# ADNS-9800.net
KiCad netlist of a schematic drawn in EAGLE
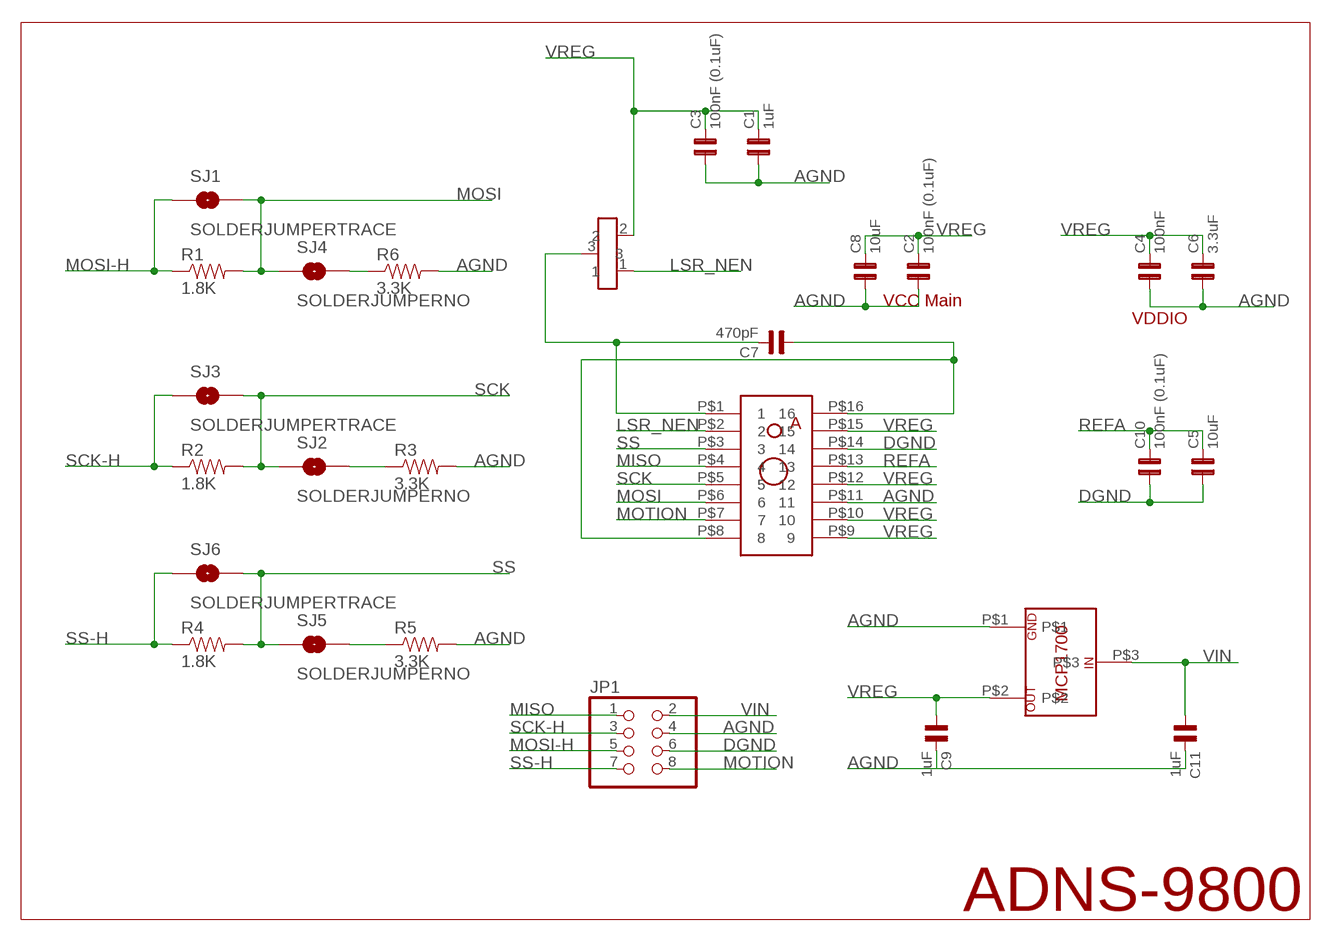
[diagram p0: schematic, sheet 1]

(export (version "E")
  (design (tool "Eeschema 10.0.6"))
  (components
    (comp (ref "C1")
      (value "1uF")
      (footprint "eagle-import:0603")
      (libsource (lib "eagle-import") (part "C0603"))
    )
    (comp (ref "C2")
      (value "100nF (0.1uF)")
      (footprint "eagle-import:0603")
      (libsource (lib "eagle-import") (part "C0603"))
    )
    (comp (ref "C3")
      (value "100nF (0.1uF)")
      (footprint "eagle-import:0603")
      (libsource (lib "eagle-import") (part "C0603"))
    )
    (comp (ref "C4")
      (value "100nF")
      (footprint "eagle-import:0603")
      (libsource (lib "eagle-import") (part "C0603"))
    )
    (comp (ref "C5")
      (value "10uF")
      (footprint "eagle-import:0603")
      (libsource (lib "eagle-import") (part "C0603"))
    )
    (comp (ref "C6")
      (value "3.3uF")
      (footprint "eagle-import:0603")
      (libsource (lib "eagle-import") (part "C0603"))
    )
    (comp (ref "C7")
      (value "470pF")
      (footprint "eagle-import:0603")
      (libsource (lib "eagle-import") (part "C0603"))
    )
    (comp (ref "C8")
      (value "10uF")
      (footprint "eagle-import:0603")
      (libsource (lib "eagle-import") (part "C0603"))
    )
    (comp (ref "C9")
      (value "1uF")
      (footprint "eagle-import:0603")
      (libsource (lib "eagle-import") (part "C0603"))
    )
    (comp (ref "C10")
      (value "100nF (0.1uF)")
      (footprint "eagle-import:0603")
      (libsource (lib "eagle-import") (part "C0603"))
    )
    (comp (ref "C11")
      (value "1uF")
      (footprint "eagle-import:0603")
      (libsource (lib "eagle-import") (part "C0603"))
    )
    (comp (ref "JP1")
      (value "PINHD-2X4")
      (footprint "eagle-import:2X04")
      (libsource (lib "eagle-import") (part "PINHD-2X4"))
    )
    (comp (ref "Q1")
      (value "TRANSISTOR_SC-75")
      (footprint "eagle-import:SC-75_TRANSISTOR")
      (libsource (lib "eagle-import") (part "TRANSISTOR_SC-75"))
    )
    (comp (ref "R1")
      (value "1.8K")
      (footprint "eagle-import:0603-RES")
      (libsource (lib "eagle-import") (part "RESISTOR0603-RES"))
    )
    (comp (ref "R2")
      (value "1.8K")
      (footprint "eagle-import:0603-RES")
      (libsource (lib "eagle-import") (part "RESISTOR0603-RES"))
    )
    (comp (ref "R3")
      (value "3.3K")
      (footprint "eagle-import:0603-RES")
      (libsource (lib "eagle-import") (part "RESISTOR0603-RES"))
    )
    (comp (ref "R4")
      (value "1.8K")
      (footprint "eagle-import:0603-RES")
      (libsource (lib "eagle-import") (part "RESISTOR0603-RES"))
    )
    (comp (ref "R5")
      (value "3.3K")
      (footprint "eagle-import:0603-RES")
      (libsource (lib "eagle-import") (part "RESISTOR0603-RES"))
    )
    (comp (ref "R6")
      (value "3.3K")
      (footprint "eagle-import:0603-RES")
      (libsource (lib "eagle-import") (part "RESISTOR0603-RES"))
    )
    (comp (ref "SJ1")
      (value "SOLDERJUMPERTRACE")
      (footprint "eagle-import:SJ_2S-TRACE")
      (libsource (lib "eagle-import") (part "SOLDERJUMPERTRACE"))
    )
    (comp (ref "SJ2")
      (value "SOLDERJUMPERNO")
      (footprint "eagle-import:SJ_2S-NO")
      (libsource (lib "eagle-import") (part "SOLDERJUMPERNO"))
    )
    (comp (ref "SJ3")
      (value "SOLDERJUMPERTRACE")
      (footprint "eagle-import:SJ_2S-TRACE")
      (libsource (lib "eagle-import") (part "SOLDERJUMPERTRACE"))
    )
    (comp (ref "SJ4")
      (value "SOLDERJUMPERNO")
      (footprint "eagle-import:SJ_2S-NO")
      (libsource (lib "eagle-import") (part "SOLDERJUMPERNO"))
    )
    (comp (ref "SJ5")
      (value "SOLDERJUMPERNO")
      (footprint "eagle-import:SJ_2S-NO")
      (libsource (lib "eagle-import") (part "SOLDERJUMPERNO"))
    )
    (comp (ref "SJ6")
      (value "SOLDERJUMPERTRACE")
      (footprint "eagle-import:SJ_2S-TRACE")
      (libsource (lib "eagle-import") (part "SOLDERJUMPERTRACE"))
    )
    (comp (ref "U$1")
      (value "AVAGO_ADNS-9500")
      (footprint "eagle-import:AVAGO_ADNS-9500")
      (libsource (lib "eagle-import") (part "AVAGO_ADNS-9500"))
    )
    (comp (ref "U$2")
      (value "MCP1700__LDO")
      (footprint "eagle-import:MCP1700__LDO")
      (libsource (lib "eagle-import") (part "MCP1700__LDO"))
    )
  )
  (nets
    (net (code "1") (name "/AGND") (class "Default")
      (node (ref "C1") (pin "1") (pinfunction "1_1") (pintype "passive"))
      (node (ref "C11") (pin "2") (pinfunction "2_2") (pintype "passive"))
      (node (ref "C2") (pin "1") (pinfunction "1_1") (pintype "passive"))
      (node (ref "C3") (pin "1") (pinfunction "1_1") (pintype "passive"))
      (node (ref "C4") (pin "1") (pinfunction "1_1") (pintype "passive"))
      (node (ref "C6") (pin "1") (pinfunction "1_1") (pintype "passive"))
      (node (ref "C8") (pin "1") (pinfunction "1_1") (pintype "passive"))
      (node (ref "C9") (pin "2") (pinfunction "2_2") (pintype "passive"))
      (node (ref "JP1") (pin "4") (pinfunction "4_4") (pintype "passive"))
      (node (ref "R3") (pin "2") (pinfunction "2_2") (pintype "passive"))
      (node (ref "R5") (pin "2") (pinfunction "2_2") (pintype "passive"))
      (node (ref "R6") (pin "2") (pinfunction "2_2") (pintype "passive"))
      (node (ref "U$1") (pin "P$11") (pinfunction "11_P$11") (pintype "bidirectional"))
      (node (ref "U$2") (pin "P$1") (pinfunction "P$1_P$1") (pintype "bidirectional"))
    )
    (net (code "2") (name "/DGND") (class "Default")
      (node (ref "C10") (pin "1") (pinfunction "1_1") (pintype "passive"))
      (node (ref "C5") (pin "1") (pinfunction "1_1") (pintype "passive"))
      (node (ref "JP1") (pin "6") (pinfunction "6_6") (pintype "passive"))
      (node (ref "U$1") (pin "P$14") (pinfunction "14_P$14") (pintype "bidirectional"))
    )
    (net (code "3") (name "/LSR_NEN") (class "Default")
      (node (ref "Q1") (pin "1") (pinfunction "1_1") (pintype "bidirectional"))
      (node (ref "U$1") (pin "P$2") (pinfunction "2_P$2") (pintype "bidirectional"))
    )
    (net (code "4") (name "/MISO") (class "Default")
      (node (ref "JP1") (pin "1") (pinfunction "1_1") (pintype "passive"))
      (node (ref "U$1") (pin "P$4") (pinfunction "4_P$4") (pintype "bidirectional"))
    )
    (net (code "5") (name "/MOSI") (class "Default")
      (node (ref "R1") (pin "2") (pinfunction "2_2") (pintype "passive"))
      (node (ref "SJ1") (pin "2") (pinfunction "2_2") (pintype "passive"))
      (node (ref "SJ4") (pin "1") (pinfunction "1_1") (pintype "passive"))
      (node (ref "U$1") (pin "P$6") (pinfunction "6_P$6") (pintype "bidirectional"))
    )
    (net (code "6") (name "/MOSI-H") (class "Default")
      (node (ref "JP1") (pin "5") (pinfunction "5_5") (pintype "passive"))
      (node (ref "R1") (pin "1") (pinfunction "1_1") (pintype "passive"))
      (node (ref "SJ1") (pin "1") (pinfunction "1_1") (pintype "passive"))
    )
    (net (code "7") (name "/MOTION") (class "Default")
      (node (ref "JP1") (pin "8") (pinfunction "8_8") (pintype "passive"))
      (node (ref "U$1") (pin "P$7") (pinfunction "7_P$7") (pintype "bidirectional"))
    )
    (net (code "8") (name "/REFA") (class "Default")
      (node (ref "C10") (pin "2") (pinfunction "2_2") (pintype "passive"))
      (node (ref "C5") (pin "2") (pinfunction "2_2") (pintype "passive"))
      (node (ref "U$1") (pin "P$13") (pinfunction "13_P$13") (pintype "bidirectional"))
    )
    (net (code "9") (name "/SCK") (class "Default")
      (node (ref "R2") (pin "2") (pinfunction "2_2") (pintype "passive"))
      (node (ref "SJ2") (pin "1") (pinfunction "1_1") (pintype "passive"))
      (node (ref "SJ3") (pin "2") (pinfunction "2_2") (pintype "passive"))
      (node (ref "U$1") (pin "P$5") (pinfunction "5_P$5") (pintype "bidirectional"))
    )
    (net (code "10") (name "/SCK-H") (class "Default")
      (node (ref "JP1") (pin "3") (pinfunction "3_3") (pintype "passive"))
      (node (ref "R2") (pin "1") (pinfunction "1_1") (pintype "passive"))
      (node (ref "SJ3") (pin "1") (pinfunction "1_1") (pintype "passive"))
    )
    (net (code "11") (name "/SS") (class "Default")
      (node (ref "R4") (pin "2") (pinfunction "2_2") (pintype "passive"))
      (node (ref "SJ5") (pin "1") (pinfunction "1_1") (pintype "passive"))
      (node (ref "SJ6") (pin "2") (pinfunction "2_2") (pintype "passive"))
      (node (ref "U$1") (pin "P$3") (pinfunction "3_P$3") (pintype "bidirectional"))
    )
    (net (code "12") (name "/SS-H") (class "Default")
      (node (ref "JP1") (pin "7") (pinfunction "7_7") (pintype "passive"))
      (node (ref "R4") (pin "1") (pinfunction "1_1") (pintype "passive"))
      (node (ref "SJ6") (pin "1") (pinfunction "1_1") (pintype "passive"))
    )
    (net (code "13") (name "/VIN") (class "Default")
      (node (ref "C11") (pin "1") (pinfunction "1_1") (pintype "passive"))
      (node (ref "JP1") (pin "2") (pinfunction "2_2") (pintype "passive"))
      (node (ref "U$2") (pin "P$3") (pinfunction "P$3_P$3") (pintype "bidirectional"))
    )
    (net (code "14") (name "/VREG") (class "Default")
      (node (ref "C1") (pin "2") (pinfunction "2_2") (pintype "passive"))
      (node (ref "C2") (pin "2") (pinfunction "2_2") (pintype "passive"))
      (node (ref "C3") (pin "2") (pinfunction "2_2") (pintype "passive"))
      (node (ref "C4") (pin "2") (pinfunction "2_2") (pintype "passive"))
      (node (ref "C6") (pin "2") (pinfunction "2_2") (pintype "passive"))
      (node (ref "C8") (pin "2") (pinfunction "2_2") (pintype "passive"))
      (node (ref "C9") (pin "1") (pinfunction "1_1") (pintype "passive"))
      (node (ref "Q1") (pin "2") (pinfunction "2_2") (pintype "bidirectional"))
      (node (ref "U$1") (pin "P$10") (pinfunction "10_P$10") (pintype "bidirectional"))
      (node (ref "U$1") (pin "P$12") (pinfunction "12_P$12") (pintype "bidirectional"))
      (node (ref "U$1") (pin "P$15") (pinfunction "15_P$15") (pintype "bidirectional"))
      (node (ref "U$1") (pin "P$9") (pinfunction "9_P$9") (pintype "bidirectional"))
      (node (ref "U$2") (pin "P$2") (pinfunction "P$2_P$2") (pintype "bidirectional"))
    )
    (net (code "15") (name "Net-(R3-Pad1)") (class "Default")
      (node (ref "R3") (pin "1") (pinfunction "1_1") (pintype "passive"))
      (node (ref "SJ2") (pin "2") (pinfunction "2_2") (pintype "passive"))
    )
    (net (code "16") (name "Net-(R5-Pad1)") (class "Default")
      (node (ref "R5") (pin "1") (pinfunction "1_1") (pintype "passive"))
      (node (ref "SJ5") (pin "2") (pinfunction "2_2") (pintype "passive"))
    )
    (net (code "17") (name "Net-(R6-Pad1)") (class "Default")
      (node (ref "R6") (pin "1") (pinfunction "1_1") (pintype "passive"))
      (node (ref "SJ4") (pin "2") (pinfunction "2_2") (pintype "passive"))
    )
    (net (code "18") (name "Net-(U$1-1)") (class "Default")
      (node (ref "C7") (pin "2") (pinfunction "2_2") (pintype "passive"))
      (node (ref "Q1") (pin "3") (pinfunction "3_3") (pintype "bidirectional"))
      (node (ref "U$1") (pin "P$1") (pinfunction "1_P$1") (pintype "bidirectional"))
    )
    (net (code "19") (name "Net-(U$1-16)") (class "Default")
      (node (ref "C7") (pin "1") (pinfunction "1_1") (pintype "passive"))
      (node (ref "U$1") (pin "P$16") (pinfunction "16_P$16") (pintype "bidirectional"))
      (node (ref "U$1") (pin "P$8") (pinfunction "8_P$8") (pintype "bidirectional"))
    )
  )
)
